# ATtiny-313.net
KiCad netlist of a schematic drawn in EAGLE
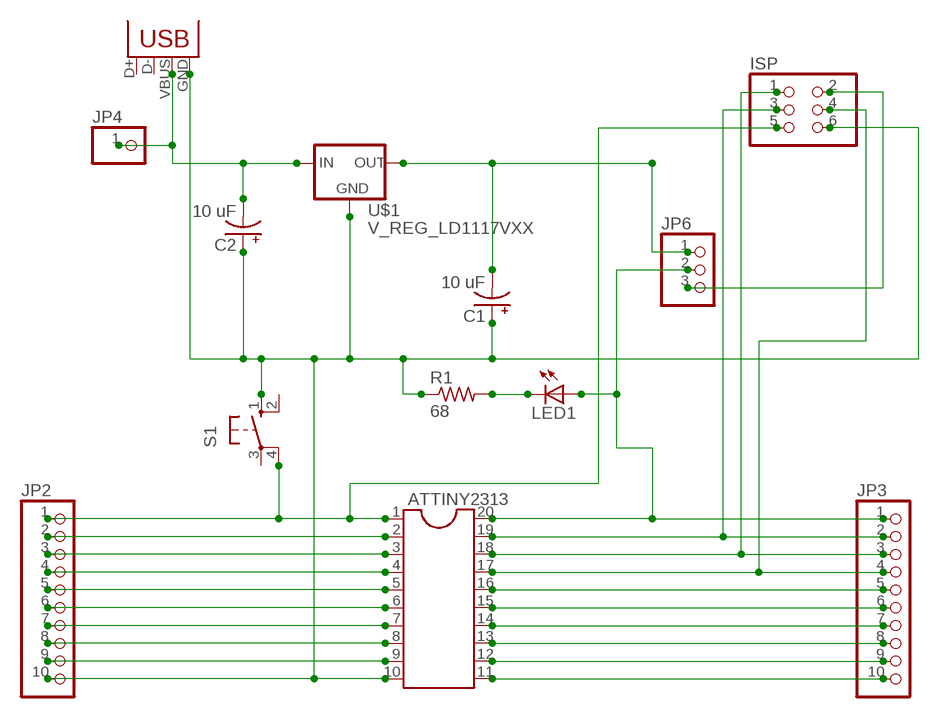
[diagram p0: schematic, sheet 1]

(export (version "E")
  (design (tool "Eeschema 10.0.6"))
  (components
    (comp (ref "ATTINY2313")
      (value "DIL20S")
      (footprint "eagle-import:SOCKET-20")
      (libsource (lib "eagle-import") (part "DIL20S"))
    )
    (comp (ref "C1")
      (value "10 uF")
      (footprint "eagle-import:E1,8-4")
      (libsource (lib "eagle-import") (part "CPOL-USE1.8-4"))
    )
    (comp (ref "C2")
      (value "10 uF")
      (footprint "eagle-import:E1,8-4")
      (libsource (lib "eagle-import") (part "CPOL-USE1.8-4"))
    )
    (comp (ref "ISP")
      (value "PINHD-2X3")
      (footprint "eagle-import:2X03")
      (libsource (lib "eagle-import") (part "PINHD-2X3"))
    )
    (comp (ref "JP1")
      (value "USB-B")
      (footprint "eagle-import:USB-B-PTH")
      (libsource (lib "eagle-import") (part "USBPTH"))
    )
    (comp (ref "JP2")
      (value "PINHD-1X10")
      (footprint "eagle-import:1X10")
      (libsource (lib "eagle-import") (part "PINHD-1X10"))
    )
    (comp (ref "JP3")
      (value "PINHD-1X10")
      (footprint "eagle-import:1X10")
      (libsource (lib "eagle-import") (part "PINHD-1X10"))
    )
    (comp (ref "JP4")
      (value "PINHD-1X1")
      (footprint "eagle-import:1X01")
      (libsource (lib "eagle-import") (part "PINHD-1X1"))
    )
    (comp (ref "JP6")
      (value "PINHD-1X3")
      (footprint "eagle-import:1X03")
      (libsource (lib "eagle-import") (part "PINHD-1X3"))
    )
    (comp (ref "LED1")
      (value "LED5MM")
      (footprint "eagle-import:LED5MM")
      (libsource (lib "eagle-import") (part "LED5MM"))
    )
    (comp (ref "R1")
      (value "68")
      (footprint "eagle-import:0207_10")
      (libsource (lib "eagle-import") (part "R-US_0207/10"))
    )
    (comp (ref "S1")
      (value "10-XX")
      (footprint "eagle-import:B3F-10XX")
      (fields (field (name "MPN") "B3F-1000"))
      (libsource (lib "eagle-import") (part "10-XX"))
    )
    (comp (ref "U$1")
      (value "V_REG_LD1117VXX")
      (footprint "eagle-import:78XXL")
      (libsource (lib "eagle-import") (part "V_REG_LD1117VXX"))
    )
  )
  (nets
    (net (code "1") (name "Net-(ATTINY2313-Pad2)") (class "Default")
      (node (ref "ATTINY2313") (pin "2") (pinfunction "2_2") (pintype "passive"))
      (node (ref "JP2") (pin "2") (pinfunction "2_2") (pintype "passive"))
    )
    (net (code "2") (name "Net-(ATTINY2313-Pad3)") (class "Default")
      (node (ref "ATTINY2313") (pin "3") (pinfunction "3_3") (pintype "passive"))
      (node (ref "JP2") (pin "3") (pinfunction "3_3") (pintype "passive"))
    )
    (net (code "3") (name "Net-(ATTINY2313-Pad4)") (class "Default")
      (node (ref "ATTINY2313") (pin "4") (pinfunction "4_4") (pintype "passive"))
      (node (ref "JP2") (pin "4") (pinfunction "4_4") (pintype "passive"))
    )
    (net (code "4") (name "Net-(ATTINY2313-Pad5)") (class "Default")
      (node (ref "ATTINY2313") (pin "5") (pinfunction "5_5") (pintype "passive"))
      (node (ref "JP2") (pin "5") (pinfunction "5_5") (pintype "passive"))
    )
    (net (code "5") (name "Net-(ATTINY2313-Pad6)") (class "Default")
      (node (ref "ATTINY2313") (pin "6") (pinfunction "6_6") (pintype "passive"))
      (node (ref "JP2") (pin "6") (pinfunction "6_6") (pintype "passive"))
    )
    (net (code "6") (name "Net-(ATTINY2313-Pad7)") (class "Default")
      (node (ref "ATTINY2313") (pin "7") (pinfunction "7_7") (pintype "passive"))
      (node (ref "JP2") (pin "7") (pinfunction "7_7") (pintype "passive"))
    )
    (net (code "7") (name "Net-(ATTINY2313-Pad8)") (class "Default")
      (node (ref "ATTINY2313") (pin "8") (pinfunction "8_8") (pintype "passive"))
      (node (ref "JP2") (pin "8") (pinfunction "8_8") (pintype "passive"))
    )
    (net (code "8") (name "Net-(ATTINY2313-Pad9)") (class "Default")
      (node (ref "ATTINY2313") (pin "9") (pinfunction "9_9") (pintype "passive"))
      (node (ref "JP2") (pin "9") (pinfunction "9_9") (pintype "passive"))
    )
    (net (code "9") (name "Net-(ATTINY2313-Pad11)") (class "Default")
      (node (ref "ATTINY2313") (pin "11") (pinfunction "11_11") (pintype "passive"))
      (node (ref "JP3") (pin "10") (pinfunction "10_10") (pintype "passive"))
    )
    (net (code "10") (name "Net-(ATTINY2313-Pad12)") (class "Default")
      (node (ref "ATTINY2313") (pin "12") (pinfunction "12_12") (pintype "passive"))
      (node (ref "JP3") (pin "9") (pinfunction "9_9") (pintype "passive"))
    )
    (net (code "11") (name "Net-(ATTINY2313-Pad13)") (class "Default")
      (node (ref "ATTINY2313") (pin "13") (pinfunction "13_13") (pintype "passive"))
      (node (ref "JP3") (pin "8") (pinfunction "8_8") (pintype "passive"))
    )
    (net (code "12") (name "Net-(ATTINY2313-Pad14)") (class "Default")
      (node (ref "ATTINY2313") (pin "14") (pinfunction "14_14") (pintype "passive"))
      (node (ref "JP3") (pin "7") (pinfunction "7_7") (pintype "passive"))
    )
    (net (code "13") (name "Net-(ATTINY2313-Pad15)") (class "Default")
      (node (ref "ATTINY2313") (pin "15") (pinfunction "15_15") (pintype "passive"))
      (node (ref "JP3") (pin "6") (pinfunction "6_6") (pintype "passive"))
    )
    (net (code "14") (name "Net-(ATTINY2313-Pad16)") (class "Default")
      (node (ref "ATTINY2313") (pin "16") (pinfunction "16_16") (pintype "passive"))
      (node (ref "JP3") (pin "5") (pinfunction "5_5") (pintype "passive"))
    )
    (net (code "15") (name "Net-(ATTINY2313-Pad17)") (class "Default")
      (node (ref "ATTINY2313") (pin "17") (pinfunction "17_17") (pintype "passive"))
      (node (ref "ISP") (pin "4") (pinfunction "4_4") (pintype "passive"))
      (node (ref "JP3") (pin "4") (pinfunction "4_4") (pintype "passive"))
    )
    (net (code "16") (name "Net-(ATTINY2313-Pad18)") (class "Default")
      (node (ref "ATTINY2313") (pin "18") (pinfunction "18_18") (pintype "passive"))
      (node (ref "ISP") (pin "1") (pinfunction "1_1") (pintype "passive"))
      (node (ref "JP3") (pin "3") (pinfunction "3_3") (pintype "passive"))
    )
    (net (code "17") (name "Net-(ATTINY2313-Pad19)") (class "Default")
      (node (ref "ATTINY2313") (pin "19") (pinfunction "19_19") (pintype "passive"))
      (node (ref "ISP") (pin "3") (pinfunction "3_3") (pintype "passive"))
      (node (ref "JP3") (pin "2") (pinfunction "2_2") (pintype "passive"))
    )
    (net (code "18") (name "Net-(ATTINY2313-Pad20)") (class "Default")
      (node (ref "ATTINY2313") (pin "20") (pinfunction "20_20") (pintype "passive"))
      (node (ref "JP3") (pin "1") (pinfunction "1_1") (pintype "passive"))
      (node (ref "JP6") (pin "2") (pinfunction "2_2") (pintype "passive"))
      (node (ref "LED1") (pin "A") (pinfunction "A_A") (pintype "passive"))
    )
    (net (code "19") (name "Net-(ISP-Pad2)") (class "Default")
      (node (ref "ISP") (pin "2") (pinfunction "2_2") (pintype "passive"))
      (node (ref "JP6") (pin "3") (pinfunction "3_3") (pintype "passive"))
    )
    (net (code "20") (name "Net-(LED1-C)") (class "Default")
      (node (ref "LED1") (pin "K") (pinfunction "C_K") (pintype "passive"))
      (node (ref "R1") (pin "2") (pinfunction "2_2") (pintype "passive"))
    )
    (net (code "21") (name "Net-(S1-P1)") (class "Default")
      (node (ref "ATTINY2313") (pin "1") (pinfunction "1_1") (pintype "passive"))
      (node (ref "ISP") (pin "5") (pinfunction "5_5") (pintype "passive"))
      (node (ref "JP2") (pin "1") (pinfunction "1_1") (pintype "passive"))
      (node (ref "S1") (pin "4") (pinfunction "P1_4") (pintype "passive"))
    )
    (net (code "22") (name "Net-(S1-S)") (class "Default")
      (node (ref "ATTINY2313") (pin "10") (pinfunction "10_10") (pintype "passive"))
      (node (ref "C1") (pin "+") (pinfunction "+_+") (pintype "passive"))
      (node (ref "C2") (pin "+") (pinfunction "+_+") (pintype "passive"))
      (node (ref "ISP") (pin "6") (pinfunction "6_6") (pintype "passive"))
      (node (ref "JP1") (pin "GND") (pinfunction "GND_GND") (pintype "bidirectional"))
      (node (ref "JP2") (pin "10") (pinfunction "10_10") (pintype "passive"))
      (node (ref "R1") (pin "1") (pinfunction "1_1") (pintype "passive"))
      (node (ref "S1") (pin "1") (pinfunction "S_1") (pintype "passive"))
      (node (ref "U$1") (pin "IN") (pinfunction "GND_IN") (pintype "input"))
    )
    (net (code "23") (name "Net-(U$1-IN)") (class "Default")
      (node (ref "C2") (pin "-") (pinfunction "-_-") (pintype "passive"))
      (node (ref "JP1") (pin "VBUS") (pinfunction "VBUS_VBUS") (pintype "bidirectional"))
      (node (ref "JP4") (pin "1") (pinfunction "1_1") (pintype "passive"))
      (node (ref "U$1") (pin "OUT") (pinfunction "IN_OUT") (pintype "input"))
    )
    (net (code "24") (name "Net-(U$1-OUT)") (class "Default")
      (node (ref "C1") (pin "-") (pinfunction "-_-") (pintype "passive"))
      (node (ref "JP6") (pin "1") (pinfunction "1_1") (pintype "passive"))
      (node (ref "U$1") (pin "GND") (pinfunction "OUT_GND") (pintype "output"))
    )
    (net (code "25") (name "unconnected-(JP1-PadD+)") (class "Default")
      (node (ref "JP1") (pin "D+") (pinfunction "D+_D+") (pintype "bidirectional"))
    )
    (net (code "26") (name "unconnected-(JP1-PadD-)") (class "Default")
      (node (ref "JP1") (pin "D-") (pinfunction "D-_D-") (pintype "bidirectional"))
    )
    (net (code "27") (name "unconnected-(S1-P-Pad3)") (class "Default")
      (node (ref "S1") (pin "3") (pinfunction "P_3") (pintype "passive"))
    )
    (net (code "28") (name "unconnected-(S1-S1-Pad2)") (class "Default")
      (node (ref "S1") (pin "2") (pinfunction "S1_2") (pintype "passive"))
    )
  )
)
